# PISO1.net
KiCad netlist of a schematic drawn in EAGLE
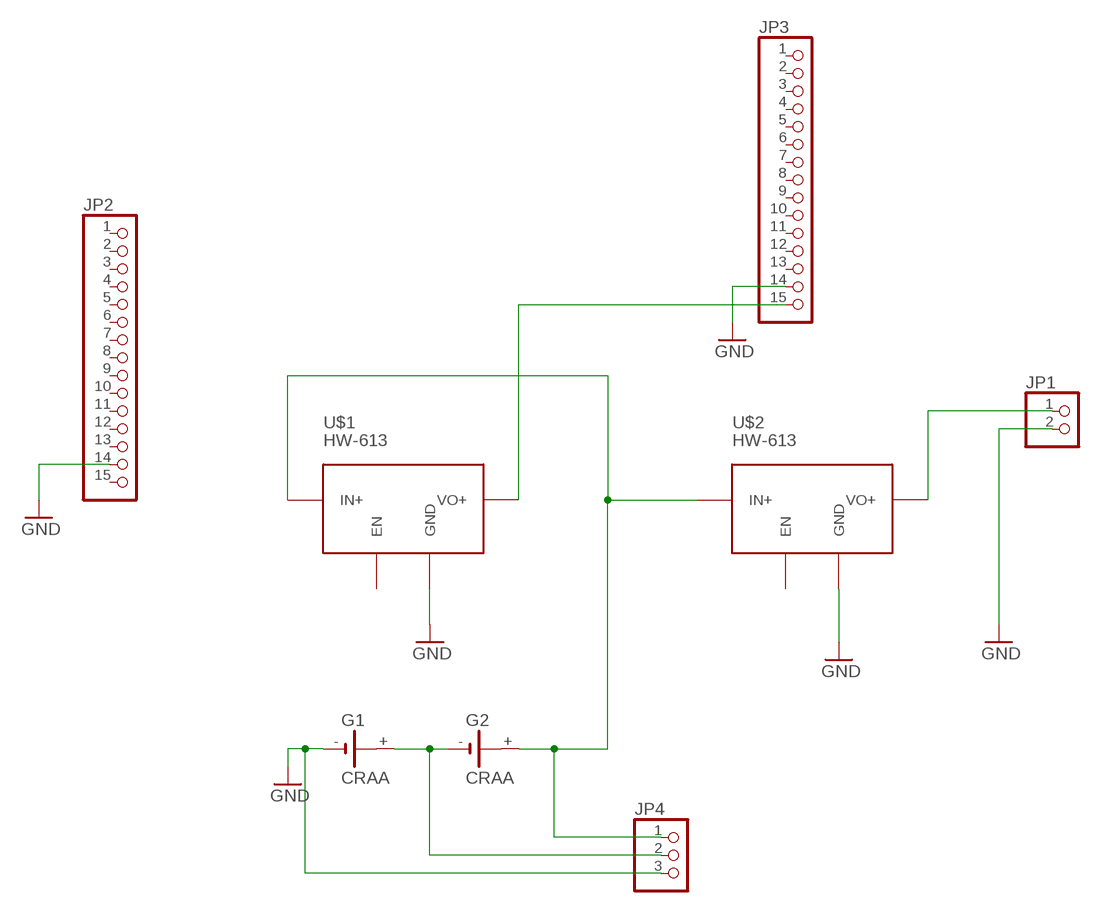
[diagram p0: schematic, sheet 1]

(export (version "E")
  (design (tool "Eeschema 10.0.6"))
  (components
    (comp (ref "G1")
      (value "CRAA")
      (footprint "eagle-import:CRAA")
      (libsource (lib "eagle-import") (part "CRAA"))
    )
    (comp (ref "G2")
      (value "CRAA")
      (footprint "eagle-import:CRAA")
      (libsource (lib "eagle-import") (part "CRAA"))
    )
    (comp (ref "JP1")
      (value "PINHD-1X2/90")
      (footprint "eagle-import:1X02_90")
      (libsource (lib "eagle-import") (part "PINHD-1X2/90"))
    )
    (comp (ref "JP2")
      (value "PINHD-1X15")
      (footprint "eagle-import:1X15")
      (libsource (lib "eagle-import") (part "PINHD-1X15"))
    )
    (comp (ref "JP3")
      (value "PINHD-1X15")
      (footprint "eagle-import:1X15")
      (libsource (lib "eagle-import") (part "PINHD-1X15"))
    )
    (comp (ref "JP4")
      (value "PINHD-1X3/90")
      (footprint "eagle-import:1X03_90")
      (libsource (lib "eagle-import") (part "PINHD-1X3/90"))
    )
    (comp (ref "U$1")
      (value "HW-613")
      (footprint "eagle-import:HW-613")
      (libsource (lib "eagle-import") (part "HW-613"))
    )
    (comp (ref "U$2")
      (value "HW-613")
      (footprint "eagle-import:HW-613")
      (libsource (lib "eagle-import") (part "HW-613"))
    )
  )
  (nets
    (net (code "1") (name "GND") (class "Default")
      (node (ref "G1") (pin "-") (pinfunction "-_-") (pintype "passive"))
      (node (ref "JP1") (pin "2") (pinfunction "2_2") (pintype "passive"))
      (node (ref "JP2") (pin "14") (pinfunction "14_14") (pintype "passive"))
      (node (ref "JP3") (pin "14") (pinfunction "14_14") (pintype "passive"))
      (node (ref "JP4") (pin "3") (pinfunction "3_3") (pintype "passive"))
      (node (ref "U$1") (pin "GND") (pinfunction "GND_GND") (pintype "bidirectional"))
      (node (ref "U$2") (pin "GND") (pinfunction "GND_GND") (pintype "bidirectional"))
    )
    (net (code "2") (name "Net-(G1-Pad+)") (class "Default")
      (node (ref "G1") (pin "+") (pinfunction "+_+") (pintype "passive"))
      (node (ref "G2") (pin "-") (pinfunction "-_-") (pintype "passive"))
      (node (ref "JP4") (pin "2") (pinfunction "2_2") (pintype "passive"))
    )
    (net (code "3") (name "Net-(G2-Pad+)") (class "Default")
      (node (ref "G2") (pin "+") (pinfunction "+_+") (pintype "passive"))
      (node (ref "JP4") (pin "1") (pinfunction "1_1") (pintype "passive"))
      (node (ref "U$1") (pin "IN+") (pinfunction "IN+_IN+") (pintype "bidirectional"))
      (node (ref "U$2") (pin "IN+") (pinfunction "IN+_IN+") (pintype "bidirectional"))
    )
    (net (code "4") (name "Net-(JP1-Pad1)") (class "Default")
      (node (ref "JP1") (pin "1") (pinfunction "1_1") (pintype "passive"))
      (node (ref "U$2") (pin "VO+") (pinfunction "VO+_VO+") (pintype "bidirectional"))
    )
    (net (code "5") (name "Net-(JP3-Pad15)") (class "Default")
      (node (ref "JP3") (pin "15") (pinfunction "15_15") (pintype "passive"))
      (node (ref "U$1") (pin "VO+") (pinfunction "VO+_VO+") (pintype "bidirectional"))
    )
    (net (code "6") (name "unconnected-(G1-+-Pad+@1)") (class "Default")
      (node (ref "G1") (pin "+@1") (pinfunction "+_+@1") (pintype "passive"))
    )
    (net (code "7") (name "unconnected-(G2-+-Pad+@1)") (class "Default")
      (node (ref "G2") (pin "+@1") (pinfunction "+_+@1") (pintype "passive"))
    )
    (net (code "8") (name "unconnected-(JP2-Pad1)") (class "Default")
      (node (ref "JP2") (pin "1") (pinfunction "1_1") (pintype "passive"))
    )
    (net (code "9") (name "unconnected-(JP2-Pad2)") (class "Default")
      (node (ref "JP2") (pin "2") (pinfunction "2_2") (pintype "passive"))
    )
    (net (code "10") (name "unconnected-(JP2-Pad3)") (class "Default")
      (node (ref "JP2") (pin "3") (pinfunction "3_3") (pintype "passive"))
    )
    (net (code "11") (name "unconnected-(JP2-Pad4)") (class "Default")
      (node (ref "JP2") (pin "4") (pinfunction "4_4") (pintype "passive"))
    )
    (net (code "12") (name "unconnected-(JP2-Pad5)") (class "Default")
      (node (ref "JP2") (pin "5") (pinfunction "5_5") (pintype "passive"))
    )
    (net (code "13") (name "unconnected-(JP2-Pad6)") (class "Default")
      (node (ref "JP2") (pin "6") (pinfunction "6_6") (pintype "passive"))
    )
    (net (code "14") (name "unconnected-(JP2-Pad7)") (class "Default")
      (node (ref "JP2") (pin "7") (pinfunction "7_7") (pintype "passive"))
    )
    (net (code "15") (name "unconnected-(JP2-Pad8)") (class "Default")
      (node (ref "JP2") (pin "8") (pinfunction "8_8") (pintype "passive"))
    )
    (net (code "16") (name "unconnected-(JP2-Pad9)") (class "Default")
      (node (ref "JP2") (pin "9") (pinfunction "9_9") (pintype "passive"))
    )
    (net (code "17") (name "unconnected-(JP2-Pad10)") (class "Default")
      (node (ref "JP2") (pin "10") (pinfunction "10_10") (pintype "passive"))
    )
    (net (code "18") (name "unconnected-(JP2-Pad11)") (class "Default")
      (node (ref "JP2") (pin "11") (pinfunction "11_11") (pintype "passive"))
    )
    (net (code "19") (name "unconnected-(JP2-Pad12)") (class "Default")
      (node (ref "JP2") (pin "12") (pinfunction "12_12") (pintype "passive"))
    )
    (net (code "20") (name "unconnected-(JP2-Pad13)") (class "Default")
      (node (ref "JP2") (pin "13") (pinfunction "13_13") (pintype "passive"))
    )
    (net (code "21") (name "unconnected-(JP2-Pad15)") (class "Default")
      (node (ref "JP2") (pin "15") (pinfunction "15_15") (pintype "passive"))
    )
    (net (code "22") (name "unconnected-(JP3-Pad1)") (class "Default")
      (node (ref "JP3") (pin "1") (pinfunction "1_1") (pintype "passive"))
    )
    (net (code "23") (name "unconnected-(JP3-Pad2)") (class "Default")
      (node (ref "JP3") (pin "2") (pinfunction "2_2") (pintype "passive"))
    )
    (net (code "24") (name "unconnected-(JP3-Pad3)") (class "Default")
      (node (ref "JP3") (pin "3") (pinfunction "3_3") (pintype "passive"))
    )
    (net (code "25") (name "unconnected-(JP3-Pad4)") (class "Default")
      (node (ref "JP3") (pin "4") (pinfunction "4_4") (pintype "passive"))
    )
    (net (code "26") (name "unconnected-(JP3-Pad5)") (class "Default")
      (node (ref "JP3") (pin "5") (pinfunction "5_5") (pintype "passive"))
    )
    (net (code "27") (name "unconnected-(JP3-Pad6)") (class "Default")
      (node (ref "JP3") (pin "6") (pinfunction "6_6") (pintype "passive"))
    )
    (net (code "28") (name "unconnected-(JP3-Pad7)") (class "Default")
      (node (ref "JP3") (pin "7") (pinfunction "7_7") (pintype "passive"))
    )
    (net (code "29") (name "unconnected-(JP3-Pad8)") (class "Default")
      (node (ref "JP3") (pin "8") (pinfunction "8_8") (pintype "passive"))
    )
    (net (code "30") (name "unconnected-(JP3-Pad9)") (class "Default")
      (node (ref "JP3") (pin "9") (pinfunction "9_9") (pintype "passive"))
    )
    (net (code "31") (name "unconnected-(JP3-Pad10)") (class "Default")
      (node (ref "JP3") (pin "10") (pinfunction "10_10") (pintype "passive"))
    )
    (net (code "32") (name "unconnected-(JP3-Pad11)") (class "Default")
      (node (ref "JP3") (pin "11") (pinfunction "11_11") (pintype "passive"))
    )
    (net (code "33") (name "unconnected-(JP3-Pad12)") (class "Default")
      (node (ref "JP3") (pin "12") (pinfunction "12_12") (pintype "passive"))
    )
    (net (code "34") (name "unconnected-(JP3-Pad13)") (class "Default")
      (node (ref "JP3") (pin "13") (pinfunction "13_13") (pintype "passive"))
    )
    (net (code "35") (name "unconnected-(U$1-PadEN)") (class "Default")
      (node (ref "U$1") (pin "EN") (pinfunction "EN_EN") (pintype "bidirectional"))
    )
    (net (code "36") (name "unconnected-(U$2-PadEN)") (class "Default")
      (node (ref "U$2") (pin "EN") (pinfunction "EN_EN") (pintype "bidirectional"))
    )
  )
)
